# SCH_card_2024-08-02.net
KiCad netlist of a schematic drawn in EasyEDA
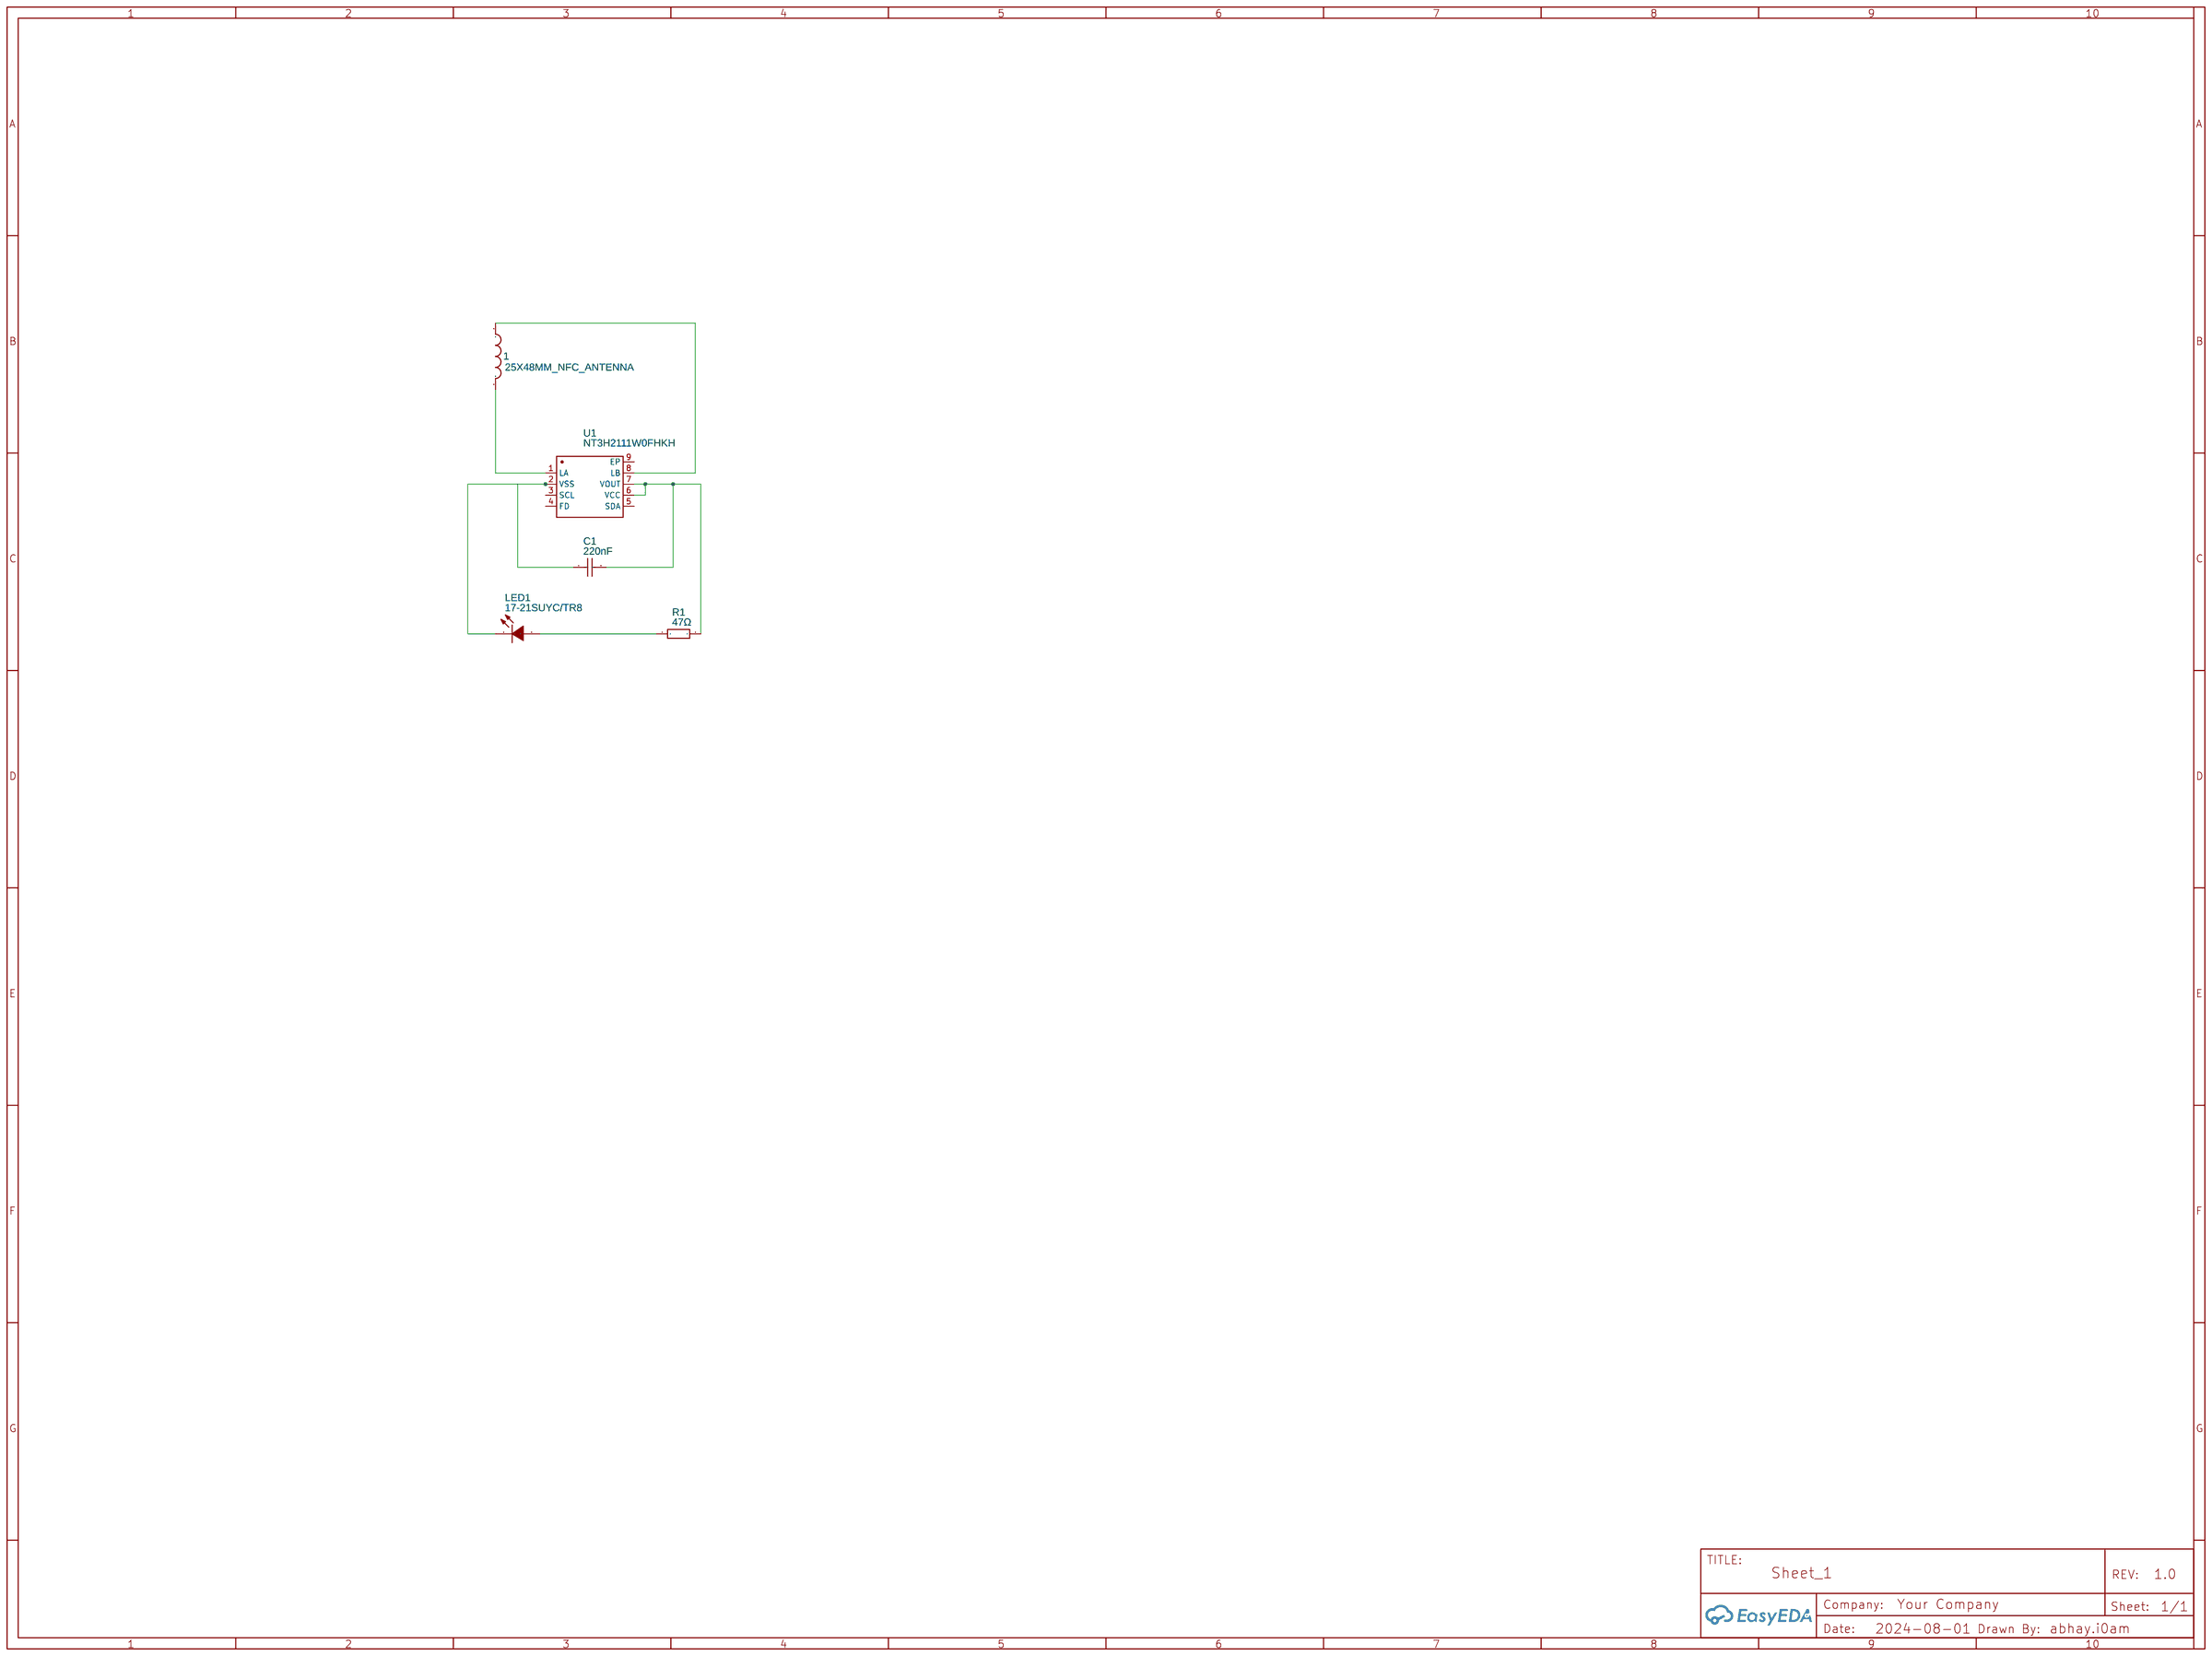
[diagram p0: schematic sheet]

(export (version "E")
  (design (tool "Eeschema 10.0.6"))
  (components
    (comp (ref "1") (value "25X48MM_NFC_ANTENNA") (libsource (lib "") (part "25X48MM_NFC_ANTENNA")))
    (comp (ref "C1")
      (value "220nF")
      (fields
        (field (name "Manufacturer Part") "CL10B224KA8NNNC")
        (field (name "Manufacturer") "SAMSUNG(三星)")
      )
      (libsource (lib "") (part "CL10B224KA8NNNC"))
    )
    (comp (ref "LED1")
      (value "17-21SUYC/TR8")
      (fields (field (name "Manufacturer Part") "KT-0805黄灯") (field (name "Manufacturer") "KENTO"))
      (libsource (lib "") (part "17-21SUYC/TR8"))
    )
    (comp (ref "R1")
      (value "47Ω")
      (fields
        (field (name "Manufacturer Part") "0603WAF470JT5E")
        (field (name "Manufacturer") "UNI-ROYAL(厚声)")
      )
      (libsource (lib "") (part "0603WAF470JT5E"))
    )
    (comp (ref "U1")
      (value "NT3H2111W0FHKH")
      (fields (field (name "Manufacturer") "NXP(恩智浦)"))
      (libsource (lib "") (part "NT3H2111W0FHKH"))
    )
  )
  (nets
    (net (code "1") (name "Net-(LED1-+)") (class "Default")
      (node (ref "LED1") (pin "1") (pinfunction "+_1") (pintype "unspecified"))
      (node (ref "R1") (pin "1") (pinfunction "1_1") (pintype "input"))
    )
    (net (code "2") (name "Net-(LED1--)") (class "Default")
      (node (ref "C1") (pin "1") (pinfunction "1_1") (pintype "input"))
      (node (ref "LED1") (pin "2") (pinfunction "-_2") (pintype "unspecified"))
      (node (ref "U1") (pin "2") (pinfunction "VSS_2") (pintype "unspecified"))
    )
    (net (code "3") (name "Net-(U1-LA)") (class "Default")
      (node (ref "1") (pin "P$2") (pinfunction "P$2_P$2") (pintype "bidirectional"))
      (node (ref "U1") (pin "1") (pinfunction "LA_1") (pintype "unspecified"))
    )
    (net (code "4") (name "Net-(U1-LB)") (class "Default")
      (node (ref "1") (pin "P$1") (pinfunction "P$1_P$1") (pintype "bidirectional"))
      (node (ref "U1") (pin "8") (pinfunction "LB_8") (pintype "unspecified"))
    )
    (net (code "5") (name "Net-(U1-VCC)") (class "Default")
      (node (ref "C1") (pin "2") (pinfunction "2_2") (pintype "input"))
      (node (ref "R1") (pin "2") (pinfunction "2_2") (pintype "input"))
      (node (ref "U1") (pin "6") (pinfunction "VCC_6") (pintype "unspecified"))
      (node (ref "U1") (pin "7") (pinfunction "VOUT_7") (pintype "unspecified"))
    )
    (net (code "6") (name "unconnected-(U1-EP-Pad9)") (class "Default")
      (node (ref "U1") (pin "9") (pinfunction "EP_9") (pintype "unspecified"))
    )
    (net (code "7") (name "unconnected-(U1-FD-Pad4)") (class "Default")
      (node (ref "U1") (pin "4") (pinfunction "FD_4") (pintype "unspecified"))
    )
    (net (code "8") (name "unconnected-(U1-SCL-Pad3)") (class "Default")
      (node (ref "U1") (pin "3") (pinfunction "SCL_3") (pintype "unspecified"))
    )
    (net (code "9") (name "unconnected-(U1-SDA-Pad5)") (class "Default")
      (node (ref "U1") (pin "5") (pinfunction "SDA_5") (pintype "unspecified"))
    )
  )
)
